# pushbutton.net
KiCad netlist of a schematic drawn in EAGLE
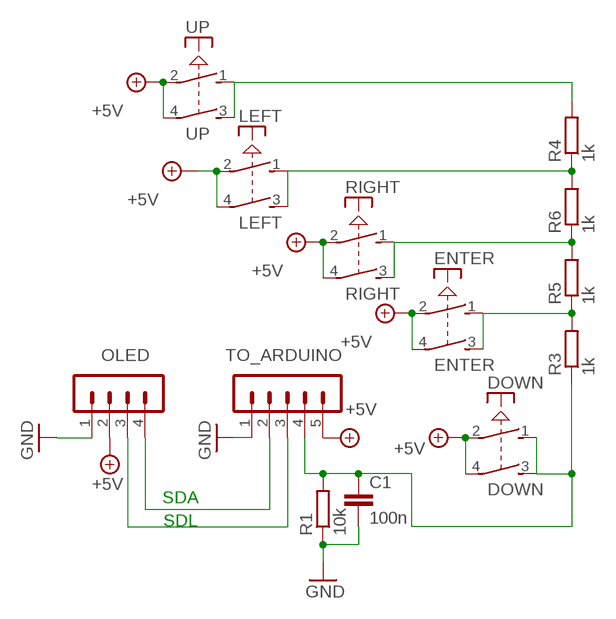
[diagram p0: schematic, sheet 1]

(export (version "E")
  (design (tool "Eeschema 10.0.6"))
  (components
    (comp (ref "C1")
      (value "100n")
      (footprint "eagle-import:C025-030X050")
      (libsource (lib "eagle-import") (part "C-EU025-030X050"))
    )
    (comp (ref "DOWN")
      (value "PVA1R")
      (footprint "eagle-import:PVA1R")
      (libsource (lib "eagle-import") (part "PVA1R"))
    )
    (comp (ref "ENTER")
      (value "PVA1R")
      (footprint "eagle-import:PVA1R")
      (libsource (lib "eagle-import") (part "PVA1R"))
    )
    (comp (ref "LEFT")
      (value "PVA1R")
      (footprint "eagle-import:PVA1R")
      (libsource (lib "eagle-import") (part "PVA1R"))
    )
    (comp (ref "OLED")
      (value "MA04-1")
      (footprint "eagle-import:MA04-1")
      (libsource (lib "eagle-import") (part "MA04-1"))
    )
    (comp (ref "R1")
      (value "10k")
      (footprint "eagle-import:0207_10")
      (libsource (lib "eagle-import") (part "R-EU_0207/10"))
    )
    (comp (ref "R3")
      (value "1k")
      (footprint "eagle-import:0207_10")
      (libsource (lib "eagle-import") (part "R-EU_0207/10"))
    )
    (comp (ref "R4")
      (value "1k")
      (footprint "eagle-import:0207_10")
      (libsource (lib "eagle-import") (part "R-EU_0207/10"))
    )
    (comp (ref "R5")
      (value "1k")
      (footprint "eagle-import:0207_10")
      (libsource (lib "eagle-import") (part "R-EU_0207/10"))
    )
    (comp (ref "R6")
      (value "1k")
      (footprint "eagle-import:0207_10")
      (libsource (lib "eagle-import") (part "R-EU_0207/10"))
    )
    (comp (ref "RIGHT")
      (value "PVA1R")
      (footprint "eagle-import:PVA1R")
      (libsource (lib "eagle-import") (part "PVA1R"))
    )
    (comp (ref "TO_ARDUINO")
      (value "MA05-1")
      (footprint "eagle-import:MA05-1")
      (libsource (lib "eagle-import") (part "MA05-1"))
    )
    (comp (ref "UP")
      (value "PVA1R")
      (footprint "eagle-import:PVA1R")
      (libsource (lib "eagle-import") (part "PVA1R"))
    )
  )
  (nets
    (net (code "1") (name "+5V") (class "Default")
      (node (ref "DOWN") (pin "2") (pinfunction "P_2") (pintype "passive"))
      (node (ref "DOWN") (pin "4") (pinfunction "P_4") (pintype "passive"))
      (node (ref "ENTER") (pin "2") (pinfunction "P_2") (pintype "passive"))
      (node (ref "ENTER") (pin "4") (pinfunction "P_4") (pintype "passive"))
      (node (ref "LEFT") (pin "2") (pinfunction "P_2") (pintype "passive"))
      (node (ref "LEFT") (pin "4") (pinfunction "P_4") (pintype "passive"))
      (node (ref "OLED") (pin "2") (pinfunction "2_2") (pintype "passive"))
      (node (ref "RIGHT") (pin "2") (pinfunction "P_2") (pintype "passive"))
      (node (ref "RIGHT") (pin "4") (pinfunction "P_4") (pintype "passive"))
      (node (ref "TO_ARDUINO") (pin "5") (pinfunction "5_5") (pintype "passive"))
      (node (ref "UP") (pin "2") (pinfunction "P_2") (pintype "passive"))
      (node (ref "UP") (pin "4") (pinfunction "P_4") (pintype "passive"))
    )
    (net (code "2") (name "GND") (class "Default")
      (node (ref "C1") (pin "2") (pinfunction "2_2") (pintype "passive"))
      (node (ref "OLED") (pin "1") (pinfunction "1_1") (pintype "passive"))
      (node (ref "R1") (pin "1") (pinfunction "1_1") (pintype "passive"))
      (node (ref "TO_ARDUINO") (pin "1") (pinfunction "1_1") (pintype "passive"))
    )
    (net (code "3") (name "Net-(DOWNA-S)") (class "Default")
      (node (ref "C1") (pin "1") (pinfunction "1_1") (pintype "passive"))
      (node (ref "DOWN") (pin "1") (pinfunction "S_1") (pintype "passive"))
      (node (ref "DOWN") (pin "3") (pinfunction "S_3") (pintype "passive"))
      (node (ref "R1") (pin "2") (pinfunction "2_2") (pintype "passive"))
      (node (ref "R3") (pin "1") (pinfunction "1_1") (pintype "passive"))
      (node (ref "TO_ARDUINO") (pin "4") (pinfunction "4_4") (pintype "passive"))
    )
    (net (code "4") (name "Net-(ENTERA-S)") (class "Default")
      (node (ref "ENTER") (pin "1") (pinfunction "S_1") (pintype "passive"))
      (node (ref "ENTER") (pin "3") (pinfunction "S_3") (pintype "passive"))
      (node (ref "R3") (pin "2") (pinfunction "2_2") (pintype "passive"))
      (node (ref "R5") (pin "1") (pinfunction "1_1") (pintype "passive"))
    )
    (net (code "5") (name "Net-(LEFTA-S)") (class "Default")
      (node (ref "LEFT") (pin "1") (pinfunction "S_1") (pintype "passive"))
      (node (ref "LEFT") (pin "3") (pinfunction "S_3") (pintype "passive"))
      (node (ref "R4") (pin "1") (pinfunction "1_1") (pintype "passive"))
      (node (ref "R6") (pin "2") (pinfunction "2_2") (pintype "passive"))
    )
    (net (code "6") (name "Net-(OLED-Pad3)") (class "Default")
      (node (ref "OLED") (pin "3") (pinfunction "3_3") (pintype "passive"))
      (node (ref "TO_ARDUINO") (pin "3") (pinfunction "3_3") (pintype "passive"))
    )
    (net (code "7") (name "Net-(OLED-Pad4)") (class "Default")
      (node (ref "OLED") (pin "4") (pinfunction "4_4") (pintype "passive"))
      (node (ref "TO_ARDUINO") (pin "2") (pinfunction "2_2") (pintype "passive"))
    )
    (net (code "8") (name "Net-(RIGHTA-S)") (class "Default")
      (node (ref "R5") (pin "2") (pinfunction "2_2") (pintype "passive"))
      (node (ref "R6") (pin "1") (pinfunction "1_1") (pintype "passive"))
      (node (ref "RIGHT") (pin "1") (pinfunction "S_1") (pintype "passive"))
      (node (ref "RIGHT") (pin "3") (pinfunction "S_3") (pintype "passive"))
    )
    (net (code "9") (name "Net-(UPA-S)") (class "Default")
      (node (ref "R4") (pin "2") (pinfunction "2_2") (pintype "passive"))
      (node (ref "UP") (pin "1") (pinfunction "S_1") (pintype "passive"))
      (node (ref "UP") (pin "3") (pinfunction "S_3") (pintype "passive"))
    )
  )
)
